# Main.net
KiCad netlist of a schematic drawn in Altium Designer
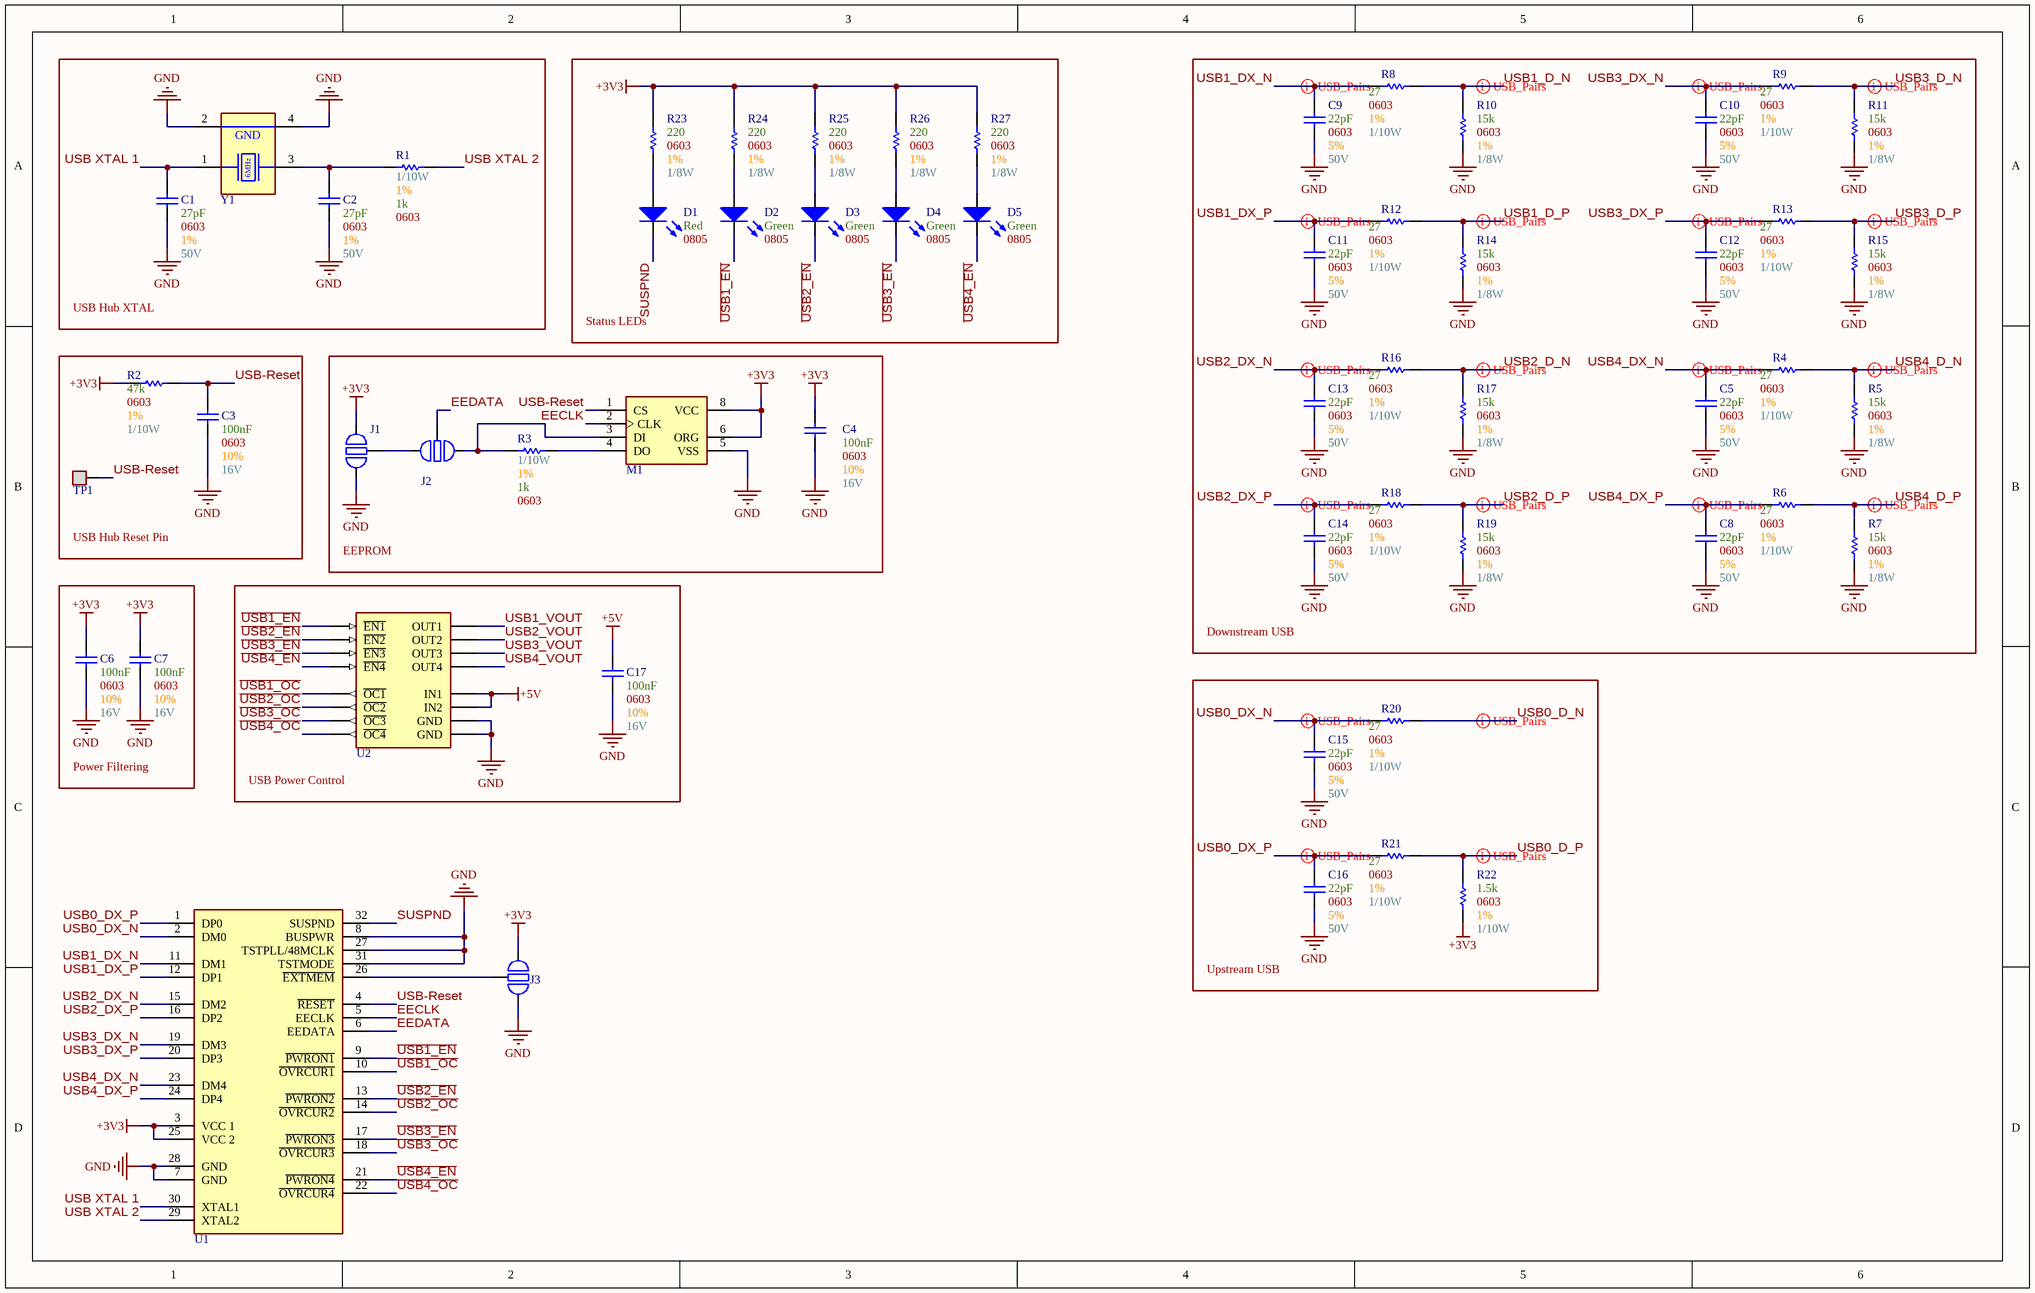
[diagram p0: Main.SchDoc]

(export (version "E")
  (design (tool "Eeschema 10.0.6"))
  (components
    (comp (ref "C1")
      (value "[Cap] 0603 27pF 1% 50V")
      (footprint "[Cap] SMD 0603")
      (description "0603N270F500CT")
      (fields
        (field (name "MAX VOLTAGE") "50V")
        (field (name "SIZE PACKAGE") "0603")
        (field (name "TOLERANCE") "1%")
        (field (name "CAPACITANCE") "27pF")
      )
      (libsource (lib "Capacitors") (part "[Cap] 0603 27pF 1% 50V"))
    )
    (comp (ref "C2")
      (value "[Cap] 0603 27pF 1% 50V")
      (footprint "[Cap] SMD 0603")
      (description "0603N270F500CT")
      (fields
        (field (name "MAX VOLTAGE") "50V")
        (field (name "SIZE PACKAGE") "0603")
        (field (name "TOLERANCE") "1%")
        (field (name "CAPACITANCE") "27pF")
      )
      (libsource (lib "Capacitors") (part "[Cap] 0603 27pF 1% 50V"))
    )
    (comp (ref "C3")
      (value "[Cap] 0603 0.1uF 10% 16V")
      (footprint "[Cap] SMD 0603")
      (description "CC0603KRX7R7BB104")
      (fields
        (field (name "MAX VOLTAGE") "16V")
        (field (name "SIZE PACKAGE") "0603")
        (field (name "TOLERANCE") "10%")
        (field (name "CAPACITANCE") "100nF")
      )
      (libsource (lib "Capacitors") (part "[Cap] 0603 0.1uF 10% 16V"))
    )
    (comp (ref "C4")
      (value "[Cap] 0603 0.1uF 10% 16V")
      (footprint "[Cap] SMD 0603")
      (description "CC0603KRX7R7BB104")
      (fields
        (field (name "MAX VOLTAGE") "16V")
        (field (name "SIZE PACKAGE") "0603")
        (field (name "TOLERANCE") "10%")
        (field (name "CAPACITANCE") "100nF")
      )
      (libsource (lib "Capacitors") (part "[Cap] 0603 0.1uF 10% 16V"))
    )
    (comp (ref "C5")
      (value "[Cap] 0603 22pF 5% 50V")
      (footprint "[Cap] SMD 0603")
      (description "CC0603JRNPO9BN240")
      (fields
        (field (name "MAX VOLTAGE") "50V")
        (field (name "SIZE PACKAGE") "0603")
        (field (name "TOLERANCE") "5%")
        (field (name "CAPACITANCE") "22pF")
      )
      (libsource (lib "Capacitors") (part "[Cap] 0603 22pF 5% 50V"))
    )
    (comp (ref "C6")
      (value "[Cap] 0603 0.1uF 10% 16V")
      (footprint "[Cap] SMD 0603")
      (description "CC0603KRX7R7BB104")
      (fields
        (field (name "MAX VOLTAGE") "16V")
        (field (name "SIZE PACKAGE") "0603")
        (field (name "TOLERANCE") "10%")
        (field (name "CAPACITANCE") "100nF")
      )
      (libsource (lib "Capacitors") (part "[Cap] 0603 0.1uF 10% 16V"))
    )
    (comp (ref "C7")
      (value "[Cap] 0603 0.1uF 10% 16V")
      (footprint "[Cap] SMD 0603")
      (description "CC0603KRX7R7BB104")
      (fields
        (field (name "MAX VOLTAGE") "16V")
        (field (name "SIZE PACKAGE") "0603")
        (field (name "TOLERANCE") "10%")
        (field (name "CAPACITANCE") "100nF")
      )
      (libsource (lib "Capacitors") (part "[Cap] 0603 0.1uF 10% 16V"))
    )
    (comp (ref "C8")
      (value "[Cap] 0603 22pF 5% 50V")
      (footprint "[Cap] SMD 0603")
      (description "CC0603JRNPO9BN240")
      (fields
        (field (name "MAX VOLTAGE") "50V")
        (field (name "SIZE PACKAGE") "0603")
        (field (name "TOLERANCE") "5%")
        (field (name "CAPACITANCE") "22pF")
      )
      (libsource (lib "Capacitors") (part "[Cap] 0603 22pF 5% 50V"))
    )
    (comp (ref "C9")
      (value "[Cap] 0603 22pF 5% 50V")
      (footprint "[Cap] SMD 0603")
      (description "CC0603JRNPO9BN240")
      (fields
        (field (name "MAX VOLTAGE") "50V")
        (field (name "SIZE PACKAGE") "0603")
        (field (name "TOLERANCE") "5%")
        (field (name "CAPACITANCE") "22pF")
      )
      (libsource (lib "Capacitors") (part "[Cap] 0603 22pF 5% 50V"))
    )
    (comp (ref "C10")
      (value "[Cap] 0603 22pF 5% 50V")
      (footprint "[Cap] SMD 0603")
      (description "CC0603JRNPO9BN240")
      (fields
        (field (name "MAX VOLTAGE") "50V")
        (field (name "SIZE PACKAGE") "0603")
        (field (name "TOLERANCE") "5%")
        (field (name "CAPACITANCE") "22pF")
      )
      (libsource (lib "Capacitors") (part "[Cap] 0603 22pF 5% 50V"))
    )
    (comp (ref "C11")
      (value "[Cap] 0603 22pF 5% 50V")
      (footprint "[Cap] SMD 0603")
      (description "CC0603JRNPO9BN240")
      (fields
        (field (name "MAX VOLTAGE") "50V")
        (field (name "SIZE PACKAGE") "0603")
        (field (name "TOLERANCE") "5%")
        (field (name "CAPACITANCE") "22pF")
      )
      (libsource (lib "Capacitors") (part "[Cap] 0603 22pF 5% 50V"))
    )
    (comp (ref "C12")
      (value "[Cap] 0603 22pF 5% 50V")
      (footprint "[Cap] SMD 0603")
      (description "CC0603JRNPO9BN240")
      (fields
        (field (name "MAX VOLTAGE") "50V")
        (field (name "SIZE PACKAGE") "0603")
        (field (name "TOLERANCE") "5%")
        (field (name "CAPACITANCE") "22pF")
      )
      (libsource (lib "Capacitors") (part "[Cap] 0603 22pF 5% 50V"))
    )
    (comp (ref "C13")
      (value "[Cap] 0603 22pF 5% 50V")
      (footprint "[Cap] SMD 0603")
      (description "CC0603JRNPO9BN240")
      (fields
        (field (name "MAX VOLTAGE") "50V")
        (field (name "SIZE PACKAGE") "0603")
        (field (name "TOLERANCE") "5%")
        (field (name "CAPACITANCE") "22pF")
      )
      (libsource (lib "Capacitors") (part "[Cap] 0603 22pF 5% 50V"))
    )
    (comp (ref "C14")
      (value "[Cap] 0603 22pF 5% 50V")
      (footprint "[Cap] SMD 0603")
      (description "CC0603JRNPO9BN240")
      (fields
        (field (name "MAX VOLTAGE") "50V")
        (field (name "SIZE PACKAGE") "0603")
        (field (name "TOLERANCE") "5%")
        (field (name "CAPACITANCE") "22pF")
      )
      (libsource (lib "Capacitors") (part "[Cap] 0603 22pF 5% 50V"))
    )
    (comp (ref "C15")
      (value "[Cap] 0603 22pF 5% 50V")
      (footprint "[Cap] SMD 0603")
      (description "CC0603JRNPO9BN240")
      (fields
        (field (name "MAX VOLTAGE") "50V")
        (field (name "SIZE PACKAGE") "0603")
        (field (name "TOLERANCE") "5%")
        (field (name "CAPACITANCE") "22pF")
      )
      (libsource (lib "Capacitors") (part "[Cap] 0603 22pF 5% 50V"))
    )
    (comp (ref "C16")
      (value "[Cap] 0603 22pF 5% 50V")
      (footprint "[Cap] SMD 0603")
      (description "CC0603JRNPO9BN240")
      (fields
        (field (name "MAX VOLTAGE") "50V")
        (field (name "SIZE PACKAGE") "0603")
        (field (name "TOLERANCE") "5%")
        (field (name "CAPACITANCE") "22pF")
      )
      (libsource (lib "Capacitors") (part "[Cap] 0603 22pF 5% 50V"))
    )
    (comp (ref "C17")
      (value "[Cap] 0603 0.1uF 10% 16V")
      (footprint "[Cap] SMD 0603")
      (description "CC0603KRX7R7BB104")
      (fields
        (field (name "MAX VOLTAGE") "16V")
        (field (name "SIZE PACKAGE") "0603")
        (field (name "TOLERANCE") "10%")
        (field (name "CAPACITANCE") "100nF")
      )
      (libsource (lib "Capacitors") (part "[Cap] 0603 0.1uF 10% 16V"))
    )
    (comp (ref "D1")
      (value "[LED] SMD 0805 Red")
      (footprint "[LED] SMD 0805")
      (description "LS R976-NR-1-0-20-R18")
      (fields (field (name "COLOR") "Red") (field (name "SIZE PACKAGE") "0805"))
      (libsource (lib "LEDs") (part "[LED] SMD 0805 Red"))
    )
    (comp (ref "D2")
      (value "[LED] SMD 0805 Green")
      (footprint "[LED] SMD 0805")
      (description "LG R971-KN-1-0-20-R18")
      (fields (field (name "COLOR") "Green") (field (name "SIZE PACKAGE") "0805"))
      (libsource (lib "LEDs") (part "[LED] SMD 0805 Green"))
    )
    (comp (ref "D3")
      (value "[LED] SMD 0805 Green")
      (footprint "[LED] SMD 0805")
      (description "LG R971-KN-1-0-20-R18")
      (fields (field (name "COLOR") "Green") (field (name "SIZE PACKAGE") "0805"))
      (libsource (lib "LEDs") (part "[LED] SMD 0805 Green"))
    )
    (comp (ref "D4")
      (value "[LED] SMD 0805 Green")
      (footprint "[LED] SMD 0805")
      (description "LG R971-KN-1-0-20-R18")
      (fields (field (name "COLOR") "Green") (field (name "SIZE PACKAGE") "0805"))
      (libsource (lib "LEDs") (part "[LED] SMD 0805 Green"))
    )
    (comp (ref "D5")
      (value "[LED] SMD 0805 Green")
      (footprint "[LED] SMD 0805")
      (description "LG R971-KN-1-0-20-R18")
      (fields (field (name "COLOR") "Green") (field (name "SIZE PACKAGE") "0805"))
      (libsource (lib "LEDs") (part "[LED] SMD 0805 Green"))
    )
    (comp (ref "J1")
      (value "[Jumper] Thru-Hole 3pin")
      (footprint "[Jumper] Thru-Hole 3pin")
      (libsource (lib "Misc Components") (part "[Jumper] Thru-Hole 3pin"))
    )
    (comp (ref "J2")
      (value "[Jumper] Thru-Hole 3pin")
      (footprint "[Jumper] Thru-Hole 3pin")
      (libsource (lib "Misc Components") (part "[Jumper] Thru-Hole 3pin"))
    )
    (comp (ref "J3")
      (value "[Jumper] Thru-Hole 3pin")
      (footprint "[Jumper] Thru-Hole 3pin")
      (libsource (lib "") (part "[Jumper] Thru-Hole 3pin_1"))
    )
    (comp (ref "M1")
      (value "[Flash] 32x16b")
      (footprint "[Flash] 32x16b")
      (description "M93C46-WMN6TP")
      (libsource (lib "Memory") (part "[Flash] 32x16b"))
    )
    (comp (ref "R1")
      (value "[1k] SMD 0603 1% 1/10W")
      (footprint "[Res] SMD 0603")
      (description "RMCF0603FT1K00")
      (fields
        (field (name "WATTAGE") "1/10W")
        (field (name "TOLERANCE") "1%")
        (field (name "RESISTANCE") "1k")
        (field (name "SIZE PACKAGE") "0603")
      )
      (libsource (lib "Resistors") (part "[1k] SMD 0603 1% 1/10W"))
    )
    (comp (ref "R2")
      (value "[47k] SMD 0603 1% 1/10W")
      (footprint "[Res] SMD 0603")
      (description "RC0603FR-0747KL")
      (fields
        (field (name "WATTAGE") "1/10W")
        (field (name "TOLERANCE") "1%")
        (field (name "RESISTANCE") "47k")
        (field (name "SIZE PACKAGE") "0603")
      )
      (libsource (lib "Resistors") (part "[47k] SMD 0603 1% 1/10W"))
    )
    (comp (ref "R3")
      (value "[1k] SMD 0603 1% 1/10W")
      (footprint "[Res] SMD 0603")
      (description "RMCF0603FT1K00")
      (fields
        (field (name "WATTAGE") "1/10W")
        (field (name "TOLERANCE") "1%")
        (field (name "RESISTANCE") "1k")
        (field (name "SIZE PACKAGE") "0603")
      )
      (libsource (lib "Resistors") (part "[1k] SMD 0603 1% 1/10W"))
    )
    (comp (ref "R4")
      (value "[27] SMD 0603 1% 1/10W")
      (footprint "[Res] SMD 0603")
      (description "MCT06030C2709FP500")
      (fields
        (field (name "WATTAGE") "1/10W")
        (field (name "TOLERANCE") "1%")
        (field (name "RESISTANCE") "27")
        (field (name "SIZE PACKAGE") "0603")
      )
      (libsource (lib "Resistors") (part "[27] SMD 0603 1% 1/10W"))
    )
    (comp (ref "R5")
      (value "[15k] SMD 0603 1% 1/8W")
      (footprint "[Res] SMD 0603")
      (description "CRCW060315K0FKEA")
      (fields
        (field (name "WATTAGE") "1/8W")
        (field (name "TOLERANCE") "1%")
        (field (name "RESISTANCE") "15k")
        (field (name "SIZE PACKAGE") "0603")
      )
      (libsource (lib "Resistors") (part "[15k] SMD 0603 1% 1/8W"))
    )
    (comp (ref "R6")
      (value "[27] SMD 0603 1% 1/10W")
      (footprint "[Res] SMD 0603")
      (description "MCT06030C2709FP500")
      (fields
        (field (name "WATTAGE") "1/10W")
        (field (name "TOLERANCE") "1%")
        (field (name "RESISTANCE") "27")
        (field (name "SIZE PACKAGE") "0603")
      )
      (libsource (lib "Resistors") (part "[27] SMD 0603 1% 1/10W"))
    )
    (comp (ref "R7")
      (value "[15k] SMD 0603 1% 1/8W")
      (footprint "[Res] SMD 0603")
      (description "CRCW060315K0FKEA")
      (fields
        (field (name "WATTAGE") "1/8W")
        (field (name "TOLERANCE") "1%")
        (field (name "RESISTANCE") "15k")
        (field (name "SIZE PACKAGE") "0603")
      )
      (libsource (lib "Resistors") (part "[15k] SMD 0603 1% 1/8W"))
    )
    (comp (ref "R8")
      (value "[27] SMD 0603 1% 1/10W")
      (footprint "[Res] SMD 0603")
      (description "MCT06030C2709FP500")
      (fields
        (field (name "WATTAGE") "1/10W")
        (field (name "TOLERANCE") "1%")
        (field (name "RESISTANCE") "27")
        (field (name "SIZE PACKAGE") "0603")
      )
      (libsource (lib "Resistors") (part "[27] SMD 0603 1% 1/10W"))
    )
    (comp (ref "R9")
      (value "[27] SMD 0603 1% 1/10W")
      (footprint "[Res] SMD 0603")
      (description "MCT06030C2709FP500")
      (fields
        (field (name "WATTAGE") "1/10W")
        (field (name "TOLERANCE") "1%")
        (field (name "RESISTANCE") "27")
        (field (name "SIZE PACKAGE") "0603")
      )
      (libsource (lib "Resistors") (part "[27] SMD 0603 1% 1/10W"))
    )
    (comp (ref "R10")
      (value "[15k] SMD 0603 1% 1/8W")
      (footprint "[Res] SMD 0603")
      (description "CRCW060315K0FKEA")
      (fields
        (field (name "WATTAGE") "1/8W")
        (field (name "TOLERANCE") "1%")
        (field (name "RESISTANCE") "15k")
        (field (name "SIZE PACKAGE") "0603")
      )
      (libsource (lib "Resistors") (part "[15k] SMD 0603 1% 1/8W"))
    )
    (comp (ref "R11")
      (value "[15k] SMD 0603 1% 1/8W")
      (footprint "[Res] SMD 0603")
      (description "CRCW060315K0FKEA")
      (fields
        (field (name "WATTAGE") "1/8W")
        (field (name "TOLERANCE") "1%")
        (field (name "RESISTANCE") "15k")
        (field (name "SIZE PACKAGE") "0603")
      )
      (libsource (lib "Resistors") (part "[15k] SMD 0603 1% 1/8W"))
    )
    (comp (ref "R12")
      (value "[27] SMD 0603 1% 1/10W")
      (footprint "[Res] SMD 0603")
      (description "MCT06030C2709FP500")
      (fields
        (field (name "WATTAGE") "1/10W")
        (field (name "TOLERANCE") "1%")
        (field (name "RESISTANCE") "27")
        (field (name "SIZE PACKAGE") "0603")
      )
      (libsource (lib "Resistors") (part "[27] SMD 0603 1% 1/10W"))
    )
    (comp (ref "R13")
      (value "[27] SMD 0603 1% 1/10W")
      (footprint "[Res] SMD 0603")
      (description "MCT06030C2709FP500")
      (fields
        (field (name "WATTAGE") "1/10W")
        (field (name "TOLERANCE") "1%")
        (field (name "RESISTANCE") "27")
        (field (name "SIZE PACKAGE") "0603")
      )
      (libsource (lib "Resistors") (part "[27] SMD 0603 1% 1/10W"))
    )
    (comp (ref "R14")
      (value "[15k] SMD 0603 1% 1/8W")
      (footprint "[Res] SMD 0603")
      (description "CRCW060315K0FKEA")
      (fields
        (field (name "WATTAGE") "1/8W")
        (field (name "TOLERANCE") "1%")
        (field (name "RESISTANCE") "15k")
        (field (name "SIZE PACKAGE") "0603")
      )
      (libsource (lib "Resistors") (part "[15k] SMD 0603 1% 1/8W"))
    )
    (comp (ref "R15")
      (value "[15k] SMD 0603 1% 1/8W")
      (footprint "[Res] SMD 0603")
      (description "CRCW060315K0FKEA")
      (fields
        (field (name "WATTAGE") "1/8W")
        (field (name "TOLERANCE") "1%")
        (field (name "RESISTANCE") "15k")
        (field (name "SIZE PACKAGE") "0603")
      )
      (libsource (lib "Resistors") (part "[15k] SMD 0603 1% 1/8W"))
    )
    (comp (ref "R16")
      (value "[27] SMD 0603 1% 1/10W")
      (footprint "[Res] SMD 0603")
      (description "MCT06030C2709FP500")
      (fields
        (field (name "WATTAGE") "1/10W")
        (field (name "TOLERANCE") "1%")
        (field (name "RESISTANCE") "27")
        (field (name "SIZE PACKAGE") "0603")
      )
      (libsource (lib "Resistors") (part "[27] SMD 0603 1% 1/10W"))
    )
    (comp (ref "R17")
      (value "[15k] SMD 0603 1% 1/8W")
      (footprint "[Res] SMD 0603")
      (description "CRCW060315K0FKEA")
      (fields
        (field (name "WATTAGE") "1/8W")
        (field (name "TOLERANCE") "1%")
        (field (name "RESISTANCE") "15k")
        (field (name "SIZE PACKAGE") "0603")
      )
      (libsource (lib "Resistors") (part "[15k] SMD 0603 1% 1/8W"))
    )
    (comp (ref "R18")
      (value "[27] SMD 0603 1% 1/10W")
      (footprint "[Res] SMD 0603")
      (description "MCT06030C2709FP500")
      (fields
        (field (name "WATTAGE") "1/10W")
        (field (name "TOLERANCE") "1%")
        (field (name "RESISTANCE") "27")
        (field (name "SIZE PACKAGE") "0603")
      )
      (libsource (lib "Resistors") (part "[27] SMD 0603 1% 1/10W"))
    )
    (comp (ref "R19")
      (value "[15k] SMD 0603 1% 1/8W")
      (footprint "[Res] SMD 0603")
      (description "CRCW060315K0FKEA")
      (fields
        (field (name "WATTAGE") "1/8W")
        (field (name "TOLERANCE") "1%")
        (field (name "RESISTANCE") "15k")
        (field (name "SIZE PACKAGE") "0603")
      )
      (libsource (lib "Resistors") (part "[15k] SMD 0603 1% 1/8W"))
    )
    (comp (ref "R20")
      (value "[27] SMD 0603 1% 1/10W")
      (footprint "[Res] SMD 0603")
      (description "MCT06030C2709FP500")
      (fields
        (field (name "WATTAGE") "1/10W")
        (field (name "TOLERANCE") "1%")
        (field (name "RESISTANCE") "27")
        (field (name "SIZE PACKAGE") "0603")
      )
      (libsource (lib "Resistors") (part "[27] SMD 0603 1% 1/10W"))
    )
    (comp (ref "R21")
      (value "[27] SMD 0603 1% 1/10W")
      (footprint "[Res] SMD 0603")
      (description "MCT06030C2709FP500")
      (fields
        (field (name "WATTAGE") "1/10W")
        (field (name "TOLERANCE") "1%")
        (field (name "RESISTANCE") "27")
        (field (name "SIZE PACKAGE") "0603")
      )
      (libsource (lib "Resistors") (part "[27] SMD 0603 1% 1/10W"))
    )
    (comp (ref "R22")
      (value "[1.5k] SMD 0603 1% 1/10W")
      (footprint "[Res] SMD 0603")
      (description "CR0603-FX-1501ELF")
      (fields
        (field (name "WATTAGE") "1/10W")
        (field (name "TOLERANCE") "1%")
        (field (name "RESISTANCE") "1.5k")
        (field (name "SIZE PACKAGE") "0603")
      )
      (libsource (lib "Resistors") (part "[1.5k] SMD 0603 1% 1/10W"))
    )
    (comp (ref "R23")
      (value "[220] SMD 0603 1% 1/10W")
      (footprint "[Res] SMD 0603")
      (description "CRGCQ0805F220R")
      (fields
        (field (name "WATTAGE") "1/8W")
        (field (name "TOLERANCE") "1%")
        (field (name "RESISTANCE") "220")
        (field (name "SIZE PACKAGE") "0603")
      )
      (libsource (lib "Resistors") (part "[220] SMD 0603 1% 1/10W"))
    )
    (comp (ref "R24")
      (value "[220] SMD 0603 1% 1/10W")
      (footprint "[Res] SMD 0603")
      (description "CRGCQ0805F220R")
      (fields
        (field (name "WATTAGE") "1/8W")
        (field (name "TOLERANCE") "1%")
        (field (name "RESISTANCE") "220")
        (field (name "SIZE PACKAGE") "0603")
      )
      (libsource (lib "Resistors") (part "[220] SMD 0603 1% 1/10W"))
    )
    (comp (ref "R25")
      (value "[220] SMD 0603 1% 1/10W")
      (footprint "[Res] SMD 0603")
      (description "CRGCQ0805F220R")
      (fields
        (field (name "WATTAGE") "1/8W")
        (field (name "TOLERANCE") "1%")
        (field (name "RESISTANCE") "220")
        (field (name "SIZE PACKAGE") "0603")
      )
      (libsource (lib "Resistors") (part "[220] SMD 0603 1% 1/10W"))
    )
    (comp (ref "R26")
      (value "[220] SMD 0603 1% 1/10W")
      (footprint "[Res] SMD 0603")
      (description "CRGCQ0805F220R")
      (fields
        (field (name "WATTAGE") "1/8W")
        (field (name "TOLERANCE") "1%")
        (field (name "RESISTANCE") "220")
        (field (name "SIZE PACKAGE") "0603")
      )
      (libsource (lib "Resistors") (part "[220] SMD 0603 1% 1/10W"))
    )
    (comp (ref "R27")
      (value "[220] SMD 0603 1% 1/10W")
      (footprint "[Res] SMD 0603")
      (description "CRGCQ0805F220R")
      (fields
        (field (name "WATTAGE") "1/8W")
        (field (name "TOLERANCE") "1%")
        (field (name "RESISTANCE") "220")
        (field (name "SIZE PACKAGE") "0603")
      )
      (libsource (lib "Resistors") (part "[220] SMD 0603 1% 1/10W"))
    )
    (comp (ref "TP1")
      (value "[THM] Thru-Hole")
      (footprint "[THM] White")
      (description "5012")
      (libsource (lib "Test Points") (part "[THM] Thru-Hole"))
    )
    (comp (ref "U1")
      (value "4port")
      (footprint "[USB Hub] USB2.0 4port")
      (description "TUSB2046BVFR")
      (libsource (lib "ICs") (part "[USB Hub] USB 2.0 4port"))
    )
    (comp (ref "U2")
      (value "[USB Power] 500mA 4port")
      (footprint "[IC] USB Hub Power Distribution")
      (description "TPS2044BDR")
      (libsource (lib "ICs") (part "[USB Power] 500mA 4port"))
    )
    (comp (ref "Y1")
      (value "[Crystal] SMD 6MHz")
      (footprint "[Crystal] SMD 6MHz")
      (description "ECS-060-18-20BM-JEN-TR")
      (libsource (lib "Crystals and Oscillators") (part "[Crystal] SMD 6MHz"))
    )
  )
  (nets
    (net (code "1") (name "+3V3") (class "Default")
      (node (ref "C4") (pin "2") (pinfunction "2_2") (pintype "passive"))
      (node (ref "C6") (pin "2") (pinfunction "2_2") (pintype "passive"))
      (node (ref "C7") (pin "2") (pinfunction "2_2") (pintype "passive"))
      (node (ref "J1") (pin "3") (pintype "passive"))
      (node (ref "J3") (pin "3") (pintype "passive"))
      (node (ref "M1") (pin "6") (pinfunction "ORG_6") (pintype "passive"))
      (node (ref "M1") (pin "8") (pinfunction "VCC_8") (pintype "passive"))
      (node (ref "R2") (pin "1") (pinfunction "1_1") (pintype "passive"))
      (node (ref "R22") (pin "1") (pinfunction "1_1") (pintype "passive"))
      (node (ref "R23") (pin "2") (pinfunction "2_2") (pintype "passive"))
      (node (ref "R24") (pin "2") (pinfunction "2_2") (pintype "passive"))
      (node (ref "R25") (pin "2") (pinfunction "2_2") (pintype "passive"))
      (node (ref "R26") (pin "2") (pinfunction "2_2") (pintype "passive"))
      (node (ref "R27") (pin "2") (pinfunction "2_2") (pintype "passive"))
      (node (ref "U1") (pin "25") (pinfunction "VCC_2_25") (pintype "passive"))
      (node (ref "U1") (pin "3") (pinfunction "VCC_1_3") (pintype "passive"))
    )
    (net (code "2") (name "+5V") (class "Default")
      (node (ref "C17") (pin "2") (pinfunction "2_2") (pintype "passive"))
      (node (ref "U2") (pin "2") (pinfunction "IN1_2") (pintype "power_in"))
      (node (ref "U2") (pin "6") (pinfunction "IN2_6") (pintype "power_in"))
    )
    (net (code "3") (name "/EECLK") (class "Default")
      (node (ref "M1") (pin "2") (pinfunction "CLK_2") (pintype "passive"))
      (node (ref "U1") (pin "5") (pinfunction "EECLK_5") (pintype "passive"))
    )
    (net (code "4") (name "/EEDATA") (class "Default")
      (node (ref "J2") (pin "2") (pinfunction "Common_2") (pintype "power_in"))
      (node (ref "U1") (pin "6") (pinfunction "EEDATA_6") (pintype "passive"))
    )
    (net (code "5") (name "/SUSPND") (class "Default")
      (node (ref "D1") (pin "2") (pinfunction "Cathode_2") (pintype "passive"))
      (node (ref "U1") (pin "32") (pinfunction "SUSPND_32") (pintype "passive"))
    )
    (net (code "6") (name "/USB XTAL 1") (class "Default")
      (node (ref "C1") (pin "2") (pinfunction "2_2") (pintype "passive"))
      (node (ref "U1") (pin "30") (pinfunction "XTAL1_30") (pintype "passive"))
      (node (ref "Y1") (pin "1") (pinfunction "XTAL1_1") (pintype "power_in"))
    )
    (net (code "7") (name "/USB XTAL 2") (class "Default")
      (node (ref "R1") (pin "2") (pinfunction "2_2") (pintype "passive"))
      (node (ref "U1") (pin "29") (pinfunction "XTAL2_29") (pintype "passive"))
    )
    (net (code "8") (name "/USB-Reset") (class "Default")
      (node (ref "C3") (pin "2") (pinfunction "2_2") (pintype "passive"))
      (node (ref "M1") (pin "1") (pinfunction "CS_1") (pintype "passive"))
      (node (ref "R2") (pin "2") (pinfunction "2_2") (pintype "passive"))
      (node (ref "TP1") (pin "1") (pinfunction "1_1") (pintype "passive"))
      (node (ref "U1") (pin "4") (pinfunction "~{RESET}_4") (pintype "passive"))
    )
    (net (code "9") (name "/USB0_DX_N") (class "Default")
      (node (ref "C15") (pin "2") (pinfunction "2_2") (pintype "passive"))
      (node (ref "R20") (pin "1") (pinfunction "1_1") (pintype "passive"))
      (node (ref "U1") (pin "2") (pinfunction "DM0_2") (pintype "passive"))
    )
    (net (code "10") (name "/USB0_DX_P") (class "Default")
      (node (ref "C16") (pin "2") (pinfunction "2_2") (pintype "passive"))
      (node (ref "R21") (pin "1") (pinfunction "1_1") (pintype "passive"))
      (node (ref "U1") (pin "1") (pinfunction "DP0_1") (pintype "passive"))
    )
    (net (code "11") (name "/USB0_D_N") (class "Default")
      (node (ref "R20") (pin "2") (pinfunction "2_2") (pintype "passive"))
    )
    (net (code "12") (name "/USB0_D_P") (class "Default")
      (node (ref "R21") (pin "2") (pinfunction "2_2") (pintype "passive"))
      (node (ref "R22") (pin "2") (pinfunction "2_2") (pintype "passive"))
    )
    (net (code "13") (name "/USB1_DX_N") (class "Default")
      (node (ref "C9") (pin "2") (pinfunction "2_2") (pintype "passive"))
      (node (ref "R8") (pin "1") (pinfunction "1_1") (pintype "passive"))
      (node (ref "U1") (pin "11") (pinfunction "DM1_11") (pintype "passive"))
    )
    (net (code "14") (name "/USB1_DX_P") (class "Default")
      (node (ref "C11") (pin "2") (pinfunction "2_2") (pintype "passive"))
      (node (ref "R12") (pin "1") (pinfunction "1_1") (pintype "passive"))
      (node (ref "U1") (pin "12") (pinfunction "DP1_12") (pintype "passive"))
    )
    (net (code "15") (name "/USB1_D_N") (class "Default")
      (node (ref "R10") (pin "2") (pinfunction "2_2") (pintype "passive"))
      (node (ref "R8") (pin "2") (pinfunction "2_2") (pintype "passive"))
    )
    (net (code "16") (name "/USB1_D_P") (class "Default")
      (node (ref "R12") (pin "2") (pinfunction "2_2") (pintype "passive"))
      (node (ref "R14") (pin "2") (pinfunction "2_2") (pintype "passive"))
    )
    (net (code "17") (name "/USB1_EN") (class "Default")
      (node (ref "D2") (pin "2") (pinfunction "Cathode_2") (pintype "passive"))
      (node (ref "U1") (pin "9") (pinfunction "~{PWRON1}_9") (pintype "passive"))
      (node (ref "U2") (pin "3") (pinfunction "~{EN1}_3") (pintype "input"))
    )
    (net (code "18") (name "/USB1_OC") (class "Default")
      (node (ref "U1") (pin "10") (pinfunction "~{OVRCUR1}_10") (pintype "passive"))
      (node (ref "U2") (pin "16") (pinfunction "~{OC1}_16") (pintype "output"))
    )
    (net (code "19") (name "/USB1_VOUT") (class "Default")
      (node (ref "U2") (pin "15") (pinfunction "OUT1_15") (pintype "power_in"))
    )
    (net (code "20") (name "/USB2_DX_N") (class "Default")
      (node (ref "C13") (pin "2") (pinfunction "2_2") (pintype "passive"))
      (node (ref "R16") (pin "1") (pinfunction "1_1") (pintype "passive"))
      (node (ref "U1") (pin "15") (pinfunction "DM2_15") (pintype "passive"))
    )
    (net (code "21") (name "/USB2_DX_P") (class "Default")
      (node (ref "C14") (pin "2") (pinfunction "2_2") (pintype "passive"))
      (node (ref "R18") (pin "1") (pinfunction "1_1") (pintype "passive"))
      (node (ref "U1") (pin "16") (pinfunction "DP2_16") (pintype "passive"))
    )
    (net (code "22") (name "/USB2_D_N") (class "Default")
      (node (ref "R16") (pin "2") (pinfunction "2_2") (pintype "passive"))
      (node (ref "R17") (pin "2") (pinfunction "2_2") (pintype "passive"))
    )
    (net (code "23") (name "/USB2_D_P") (class "Default")
      (node (ref "R18") (pin "2") (pinfunction "2_2") (pintype "passive"))
      (node (ref "R19") (pin "2") (pinfunction "2_2") (pintype "passive"))
    )
    (net (code "24") (name "/USB2_EN") (class "Default")
      (node (ref "D3") (pin "2") (pinfunction "Cathode_2") (pintype "passive"))
      (node (ref "U1") (pin "13") (pinfunction "~{PWRON2}_13") (pintype "passive"))
      (node (ref "U2") (pin "4") (pinfunction "~{EN2}_4") (pintype "input"))
    )
    (net (code "25") (name "/USB2_OC") (class "Default")
      (node (ref "U1") (pin "14") (pinfunction "~{OVRCUR2}_14") (pintype "passive"))
      (node (ref "U2") (pin "13") (pinfunction "~{OC2}_13") (pintype "output"))
    )
    (net (code "26") (name "/USB2_VOUT") (class "Default")
      (node (ref "U2") (pin "14") (pinfunction "OUT2_14") (pintype "power_in"))
    )
    (net (code "27") (name "/USB3_DX_N") (class "Default")
      (node (ref "C10") (pin "2") (pinfunction "2_2") (pintype "passive"))
      (node (ref "R9") (pin "1") (pinfunction "1_1") (pintype "passive"))
      (node (ref "U1") (pin "19") (pinfunction "DM3_19") (pintype "passive"))
    )
    (net (code "28") (name "/USB3_DX_P") (class "Default")
      (node (ref "C12") (pin "2") (pinfunction "2_2") (pintype "passive"))
      (node (ref "R13") (pin "1") (pinfunction "1_1") (pintype "passive"))
      (node (ref "U1") (pin "20") (pinfunction "DP3_20") (pintype "passive"))
    )
    (net (code "29") (name "/USB3_D_N") (class "Default")
      (node (ref "R11") (pin "2") (pinfunction "2_2") (pintype "passive"))
      (node (ref "R9") (pin "2") (pinfunction "2_2") (pintype "passive"))
    )
    (net (code "30") (name "/USB3_D_P") (class "Default")
      (node (ref "R13") (pin "2") (pinfunction "2_2") (pintype "passive"))
      (node (ref "R15") (pin "2") (pinfunction "2_2") (pintype "passive"))
    )
    (net (code "31") (name "/USB3_EN") (class "Default")
      (node (ref "D4") (pin "2") (pinfunction "Cathode_2") (pintype "passive"))
      (node (ref "U1") (pin "17") (pinfunction "~{PWRON3}_17") (pintype "passive"))
      (node (ref "U2") (pin "7") (pinfunction "~{EN3}_7") (pintype "input"))
    )
    (net (code "32") (name "/USB3_OC") (class "Default")
      (node (ref "U1") (pin "18") (pinfunction "~{OVRCUR3}_18") (pintype "passive"))
      (node (ref "U2") (pin "12") (pinfunction "~{OC3}_12") (pintype "output"))
    )
    (net (code "33") (name "/USB3_VOUT") (class "Default")
      (node (ref "U2") (pin "11") (pinfunction "OUT3_11") (pintype "power_in"))
    )
    (net (code "34") (name "/USB4_DX_N") (class "Default")
      (node (ref "C5") (pin "2") (pinfunction "2_2") (pintype "passive"))
      (node (ref "R4") (pin "1") (pinfunction "1_1") (pintype "passive"))
      (node (ref "U1") (pin "23") (pinfunction "DM4_23") (pintype "passive"))
    )
    (net (code "35") (name "/USB4_DX_P") (class "Default")
      (node (ref "C8") (pin "2") (pinfunction "2_2") (pintype "passive"))
      (node (ref "R6") (pin "1") (pinfunction "1_1") (pintype "passive"))
      (node (ref "U1") (pin "24") (pinfunction "DP4_24") (pintype "passive"))
    )
    (net (code "36") (name "/USB4_D_N") (class "Default")
      (node (ref "R4") (pin "2") (pinfunction "2_2") (pintype "passive"))
      (node (ref "R5") (pin "2") (pinfunction "2_2") (pintype "passive"))
    )
    (net (code "37") (name "/USB4_D_P") (class "Default")
      (node (ref "R6") (pin "2") (pinfunction "2_2") (pintype "passive"))
      (node (ref "R7") (pin "2") (pinfunction "2_2") (pintype "passive"))
    )
    (net (code "38") (name "/USB4_EN") (class "Default")
      (node (ref "D5") (pin "2") (pinfunction "Cathode_2") (pintype "passive"))
      (node (ref "U1") (pin "21") (pinfunction "~{PWRON4}_21") (pintype "passive"))
      (node (ref "U2") (pin "8") (pinfunction "~{EN4}_8") (pintype "input"))
    )
    (net (code "39") (name "/USB4_OC") (class "Default")
      (node (ref "U1") (pin "22") (pinfunction "~{OVRCUR4}_22") (pintype "passive"))
      (node (ref "U2") (pin "9") (pinfunction "~{OC4}_9") (pintype "output"))
    )
    (net (code "40") (name "/USB4_VOUT") (class "Default")
      (node (ref "U2") (pin "10") (pinfunction "OUT4_10") (pintype "power_in"))
    )
    (net (code "41") (name "GND") (class "Default")
      (node (ref "C1") (pin "1") (pinfunction "1_1") (pintype "passive"))
      (node (ref "C10") (pin "1") (pinfunction "1_1") (pintype "passive"))
      (node (ref "C11") (pin "1") (pinfunction "1_1") (pintype "passive"))
      (node (ref "C12") (pin "1") (pinfunction "1_1") (pintype "passive"))
      (node (ref "C13") (pin "1") (pinfunction "1_1") (pintype "passive"))
      (node (ref "C14") (pin "1") (pinfunction "1_1") (pintype "passive"))
      (node (ref "C15") (pin "1") (pinfunction "1_1") (pintype "passive"))
      (node (ref "C16") (pin "1") (pinfunction "1_1") (pintype "passive"))
      (node (ref "C17") (pin "1") (pinfunction "1_1") (pintype "passive"))
      (node (ref "C2") (pin "1") (pinfunction "1_1") (pintype "passive"))
      (node (ref "C3") (pin "1") (pinfunction "1_1") (pintype "passive"))
      (node (ref "C4") (pin "1") (pinfunction "1_1") (pintype "passive"))
      (node (ref "C5") (pin "1") (pinfunction "1_1") (pintype "passive"))
      (node (ref "C6") (pin "1") (pinfunction "1_1") (pintype "passive"))
      (node (ref "C7") (pin "1") (pinfunction "1_1") (pintype "passive"))
      (node (ref "C8") (pin "1") (pinfunction "1_1") (pintype "passive"))
      (node (ref "C9") (pin "1") (pinfunction "1_1") (pintype "passive"))
      (node (ref "J1") (pin "1") (pintype "passive"))
      (node (ref "J3") (pin "1") (pintype "passive"))
      (node (ref "M1") (pin "5") (pinfunction "VSS_5") (pintype "passive"))
      (node (ref "R10") (pin "1") (pinfunction "1_1") (pintype "passive"))
      (node (ref "R11") (pin "1") (pinfunction "1_1") (pintype "passive"))
      (node (ref "R14") (pin "1") (pinfunction "1_1") (pintype "passive"))
      (node (ref "R15") (pin "1") (pinfunction "1_1") (pintype "passive"))
      (node (ref "R17") (pin "1") (pinfunction "1_1") (pintype "passive"))
      (node (ref "R19") (pin "1") (pinfunction "1_1") (pintype "passive"))
      (node (ref "R5") (pin "1") (pinfunction "1_1") (pintype "passive"))
      (node (ref "R7") (pin "1") (pinfunction "1_1") (pintype "passive"))
      (node (ref "U1") (pin "27") (pinfunction "TSTPLL/48MCLK_27") (pintype "passive"))
      (node (ref "U1") (pin "28") (pinfunction "GND_28") (pintype "passive"))
      (node (ref "U1") (pin "31") (pinfunction "TSTMODE_31") (pintype "passive"))
      (node (ref "U1") (pin "7") (pinfunction "GND_7") (pintype "passive"))
      (node (ref "U1") (pin "8") (pinfunction "BUSPWR_8") (pintype "passive"))
      (node (ref "U2") (pin "1") (pinfunction "GND_1") (pintype "power_in"))
      (node (ref "U2") (pin "5") (pinfunction "GND_5") (pintype "power_in"))
      (node (ref "Y1") (pin "2") (pinfunction "GND_2") (pintype "power_in"))
      (node (ref "Y1") (pin "4") (pinfunction "GND_4") (pintype "power_in"))
    )
    (net (code "42") (name "Net-(D1-Anode)") (class "Default")
      (node (ref "D1") (pin "1") (pinfunction "Anode_1") (pintype "passive"))
      (node (ref "R23") (pin "1") (pinfunction "1_1") (pintype "passive"))
    )
    (net (code "43") (name "Net-(D2-Anode)") (class "Default")
      (node (ref "D2") (pin "1") (pinfunction "Anode_1") (pintype "passive"))
      (node (ref "R24") (pin "1") (pinfunction "1_1") (pintype "passive"))
    )
    (net (code "44") (name "Net-(D3-Anode)") (class "Default")
      (node (ref "D3") (pin "1") (pinfunction "Anode_1") (pintype "passive"))
      (node (ref "R25") (pin "1") (pinfunction "1_1") (pintype "passive"))
    )
    (net (code "45") (name "Net-(D4-Anode)") (class "Default")
      (node (ref "D4") (pin "1") (pinfunction "Anode_1") (pintype "passive"))
      (node (ref "R26") (pin "1") (pinfunction "1_1") (pintype "passive"))
    )
    (net (code "46") (name "Net-(D5-Anode)") (class "Default")
      (node (ref "D5") (pin "1") (pinfunction "Anode_1") (pintype "passive"))
      (node (ref "R27") (pin "1") (pinfunction "1_1") (pintype "passive"))
    )
    (net (code "47") (name "Net-(J1-Common)") (class "Default")
      (node (ref "J1") (pin "2") (pinfunction "Common_2") (pintype "power_in"))
      (node (ref "J2") (pin "3") (pintype "passive"))
    )
    (net (code "48") (name "Net-(J3-Common)") (class "Default")
      (node (ref "J3") (pin "2") (pinfunction "Common_2") (pintype "power_in"))
      (node (ref "U1") (pin "26") (pinfunction "~{EXTMEM}_26") (pintype "passive"))
    )
    (net (code "49") (name "Net-(M1-DI)") (class "Default")
      (node (ref "J2") (pin "1") (pintype "passive"))
      (node (ref "M1") (pin "3") (pinfunction "DI_3") (pintype "passive"))
      (node (ref "R3") (pin "2") (pinfunction "2_2") (pintype "passive"))
    )
    (net (code "50") (name "Net-(M1-DO)") (class "Default")
      (node (ref "M1") (pin "4") (pinfunction "DO_4") (pintype "passive"))
      (node (ref "R3") (pin "1") (pinfunction "1_1") (pintype "passive"))
    )
    (net (code "51") (name "Net-(Y1-XTAL2)") (class "Default")
      (node (ref "C2") (pin "2") (pinfunction "2_2") (pintype "passive"))
      (node (ref "R1") (pin "1") (pinfunction "1_1") (pintype "passive"))
      (node (ref "Y1") (pin "3") (pinfunction "XTAL2_3") (pintype "power_in"))
    )
  )
)
